# ZeroCrossDetector.net
KiCad netlist of a schematic drawn in Altium Designer
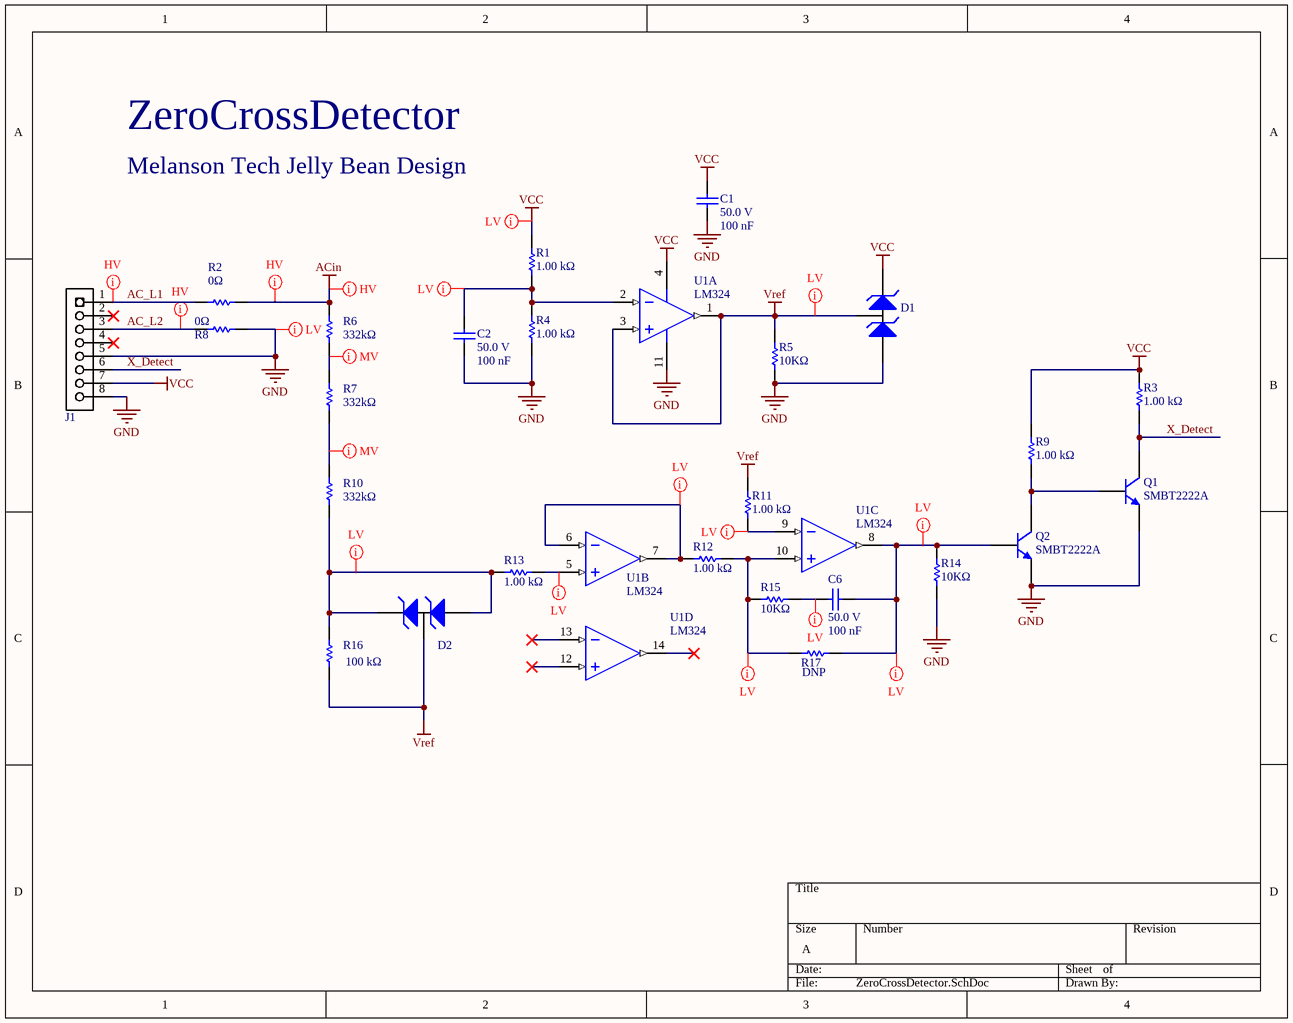
[diagram p0: ZeroCrossDetector.SchDoc]

(export (version "E")
  (design (tool "Eeschema 10.0.6"))
  (components
    (comp (ref "C1")
      (value "08055C104JAT2A")
      (footprint "Cap,0805")
      (description "Capacitor; Ceramic; Cap 0.1 uF; Tol 5%; Vol-Rtg 50 VDC; SMT; 0805; X7R; Tape & Reel")
      (fields (field (name "VOLTAGE RATING (DC)") "50.0 V") (field (name "CAPACITANCE") "100 nF"))
      (libsource (lib "Master Nov2021") (part "Cap,0805,100nf,50V,5%,08055C104JAT2A"))
    )
    (comp (ref "C2")
      (value "08055C104JAT2A")
      (footprint "Cap,0805")
      (description "Capacitor; Ceramic; Cap 0.1 uF; Tol 5%; Vol-Rtg 50 VDC; SMT; 0805; X7R; Tape & Reel")
      (fields (field (name "VOLTAGE RATING (DC)") "50.0 V") (field (name "CAPACITANCE") "100 nF"))
      (libsource (lib "Master Nov2021") (part "Cap,0805,100nf,50V,5%,08055C104JAT2A"))
    )
    (comp (ref "C6")
      (value "08055C104JAT2A")
      (footprint "Cap,0805")
      (description "Capacitor; Ceramic; Cap 0.1 uF; Tol 5%; Vol-Rtg 50 VDC; SMT; 0805; X7R; Tape & Reel")
      (fields (field (name "VOLTAGE RATING (DC)") "50.0 V") (field (name "CAPACITANCE") "100 nF"))
      (libsource (lib "Master Nov2021") (part "Cap,0805,100nf,50V,5%,08055C104JAT2A"))
    )
    (comp (ref "D1")
      (value "BAT54SLT1G")
      (footprint "SOT23-3")
      (fields (field (name "BASE PART NUMBER") "BAT54SL") (field (name "MANUFACTURER") "ON Semiconductor"))
      (libsource (lib "Master Nov2021") (part "Diode,Shottky,Array,Series,30V,200mA,BAT54SLT1G"))
    )
    (comp (ref "D2")
      (value "BAT54SLT1G")
      (footprint "SOT23-3")
      (fields (field (name "BASE PART NUMBER") "BAT54SL") (field (name "MANUFACTURER") "ON Semiconductor"))
      (libsource (lib "Master Nov2021") (part "Diode,Shottky,Array,Series,30V,200mA,BAT54SLT1G"))
    )
    (comp (ref "J1")
      (value "HEADER,0.1\",8Pin,SinlgeRow")
      (footprint "Header,8Pin,SingleRow, RA,0.1\"")
      (libsource (lib "Master Nov2021") (part "HEADER,0.1{dblquote},8Pin,SinlgeRow"))
    )
    (comp (ref "Logo1")
      (value "Open Source Logo")
      (footprint "Symbol,Open Source")
      (description "Open Source Silk Screen Logo")
      (libsource (lib "Master Mar2024") (part "Symbol,Open Source"))
    )
    (comp (ref "Q1")
      (value "SMBT2222A")
      (footprint "SOT23-3")
      (description "NPN Silicon Switching Transistor, 40 V VCEO, 600 mA IC, SOT23, Reel, Green")
      (fields (field (name "MFG P/N") "SMBT2222A"))
      (libsource (lib "Master Nov2021") (part "Trans,40V,600mA,0.33W, SMBT2222A"))
    )
    (comp (ref "Q2")
      (value "SMBT2222A")
      (footprint "SOT23-3")
      (description "NPN Silicon Switching Transistor, 40 V VCEO, 600 mA IC, SOT23, Reel, Green")
      (fields (field (name "MFG P/N") "SMBT2222A"))
      (libsource (lib "Master Nov2021") (part "Trans,40V,600mA,0.33W, SMBT2222A"))
    )
    (comp (ref "R1")
      (value "Vishay CRCW08051K00JNEA")
      (footprint "res, 0805, HD")
      (description "Res Thick Film 0805 1K Ohm 5% 0.125W(1/8W) ±200ppm/C Molded SMD Automotive Paper T/R")
      (fields
        (field (name "MANUFACTURER PART NUMBER") "CRCW08051K00JNEA")
        (field (name "RESISTANCE") "1.00 kΩ")
      )
      (libsource (lib "Master Nov2021") (part "Res,0805,1.00 kΩ,5%,200ppm,CRCW08051K00JNEA"))
    )
    (comp (ref "R2")
      (value "Res1")
      (footprint "Res,1206")
      (fields (field (name "RESISTANCE") "0Ω"))
      (libsource (lib "Master Nov2021") (part "Res,1206,Generic"))
    )
    (comp (ref "R3")
      (value "Vishay CRCW08051K00JNEA")
      (footprint "res, 0805, HD")
      (description "Res Thick Film 0805 1K Ohm 5% 0.125W(1/8W) ±200ppm/C Molded SMD Automotive Paper T/R")
      (fields
        (field (name "MANUFACTURER PART NUMBER") "CRCW08051K00JNEA")
        (field (name "RESISTANCE") "1.00 kΩ")
      )
      (libsource (lib "Master Nov2021") (part "Res,0805,1.00 kΩ,5%,200ppm,CRCW08051K00JNEA"))
    )
    (comp (ref "R4")
      (value "Vishay CRCW08051K00JNEA")
      (footprint "res, 0805, HD")
      (description "Res Thick Film 0805 1K Ohm 5% 0.125W(1/8W) ±200ppm/C Molded SMD Automotive Paper T/R")
      (fields
        (field (name "MANUFACTURER PART NUMBER") "CRCW08051K00JNEA")
        (field (name "RESISTANCE") "1.00 kΩ")
      )
      (libsource (lib "Master Nov2021") (part "Res,0805,1.00 kΩ,5%,200ppm,CRCW08051K00JNEA"))
    )
    (comp (ref "R5")
      (value "Vishay / Dale CRCW080510K0FKTA")
      (footprint "res, 0805, HD")
      (description "RES SMD 10K OHM 1% 1/8W 0805")
      (fields (field (name "RESISTANCE") "10KΩ"))
      (libsource (lib "Master Nov2021") (part "Res,0805,10.0kΩ,1%,100 ppm,CRCW080510K0FKTA"))
    )
    (comp (ref "R6")
      (value "RT0805BRD07332KL")
      (footprint "res, 0805, HD")
      (description "Thin Film Resistors - SMD 1/8W 332K ohm .1% 25ppm")
      (fields (field (name "RESISTANCE") "332kΩ"))
      (libsource (lib "Master Nov2021") (part "Res,0805,332k,0.1%,±25ppm/°C,RT0805BRD07332KL"))
    )
    (comp (ref "R7")
      (value "RT0805BRD07332KL")
      (footprint "res, 0805, HD")
      (description "Thin Film Resistors - SMD 1/8W 332K ohm .1% 25ppm")
      (fields (field (name "RESISTANCE") "332kΩ"))
      (libsource (lib "Master Nov2021") (part "Res,0805,332k,0.1%,±25ppm/°C,RT0805BRD07332KL"))
    )
    (comp (ref "R8")
      (value "Res1")
      (footprint "Res,1206")
      (fields (field (name "RESISTANCE") "0Ω"))
      (libsource (lib "Master Nov2021") (part "Res,1206,Generic"))
    )
    (comp (ref "R9")
      (value "Vishay CRCW08051K00JNEA")
      (footprint "res, 0805, HD")
      (description "Res Thick Film 0805 1K Ohm 5% 0.125W(1/8W) ±200ppm/C Molded SMD Automotive Paper T/R")
      (fields
        (field (name "MANUFACTURER PART NUMBER") "CRCW08051K00JNEA")
        (field (name "RESISTANCE") "1.00 kΩ")
      )
      (libsource (lib "Master Nov2021") (part "Res,0805,1.00 kΩ,5%,200ppm,CRCW08051K00JNEA"))
    )
    (comp (ref "R10")
      (value "RT0805BRD07332KL")
      (footprint "res, 0805, HD")
      (description "Thin Film Resistors - SMD 1/8W 332K ohm .1% 25ppm")
      (fields (field (name "RESISTANCE") "332kΩ"))
      (libsource (lib "Master Nov2021") (part "Res,0805,332k,0.1%,±25ppm/°C,RT0805BRD07332KL"))
    )
    (comp (ref "R11")
      (value "Vishay CRCW08051K00JNEA")
      (footprint "res, 0805, HD")
      (description "Res Thick Film 0805 1K Ohm 5% 0.125W(1/8W) ±200ppm/C Molded SMD Automotive Paper T/R")
      (fields
        (field (name "MANUFACTURER PART NUMBER") "CRCW08051K00JNEA")
        (field (name "RESISTANCE") "1.00 kΩ")
      )
      (libsource (lib "Master Nov2021") (part "Res,0805,1.00 kΩ,5%,200ppm,CRCW08051K00JNEA"))
    )
    (comp (ref "R12")
      (value "Vishay CRCW08051K00JNEA")
      (footprint "res, 0805, HD")
      (description "Res Thick Film 0805 1K Ohm 5% 0.125W(1/8W) ±200ppm/C Molded SMD Automotive Paper T/R")
      (fields
        (field (name "MANUFACTURER PART NUMBER") "CRCW08051K00JNEA")
        (field (name "RESISTANCE") "1.00 kΩ")
      )
      (libsource (lib "Master Nov2021") (part "Res,0805,1.00 kΩ,5%,200ppm,CRCW08051K00JNEA"))
    )
    (comp (ref "R13")
      (value "Vishay CRCW08051K00JNEA")
      (footprint "res, 0805, HD")
      (description "Res Thick Film 0805 1K Ohm 5% 0.125W(1/8W) ±200ppm/C Molded SMD Automotive Paper T/R")
      (fields
        (field (name "MANUFACTURER PART NUMBER") "CRCW08051K00JNEA")
        (field (name "RESISTANCE") "1.00 kΩ")
      )
      (libsource (lib "Master Nov2021") (part "Res,0805,1.00 kΩ,5%,200ppm,CRCW08051K00JNEA"))
    )
    (comp (ref "R14")
      (value "Vishay / Dale CRCW080510K0FKTA")
      (footprint "res, 0805, HD")
      (description "RES SMD 10K OHM 1% 1/8W 0805")
      (fields (field (name "RESISTANCE") "10KΩ"))
      (libsource (lib "Master Nov2021") (part "Res,0805,10.0kΩ,1%,100 ppm,CRCW080510K0FKTA"))
    )
    (comp (ref "R15")
      (value "Vishay / Dale CRCW080510K0FKTA")
      (footprint "res, 0805, HD")
      (description "RES SMD 10K OHM 1% 1/8W 0805")
      (fields (field (name "RESISTANCE") "10KΩ"))
      (libsource (lib "Master Nov2021") (part "Res,0805,10.0kΩ,1%,100 ppm,CRCW080510K0FKTA"))
    )
    (comp (ref "R16")
      (value "CRCW0805100KFKEA")
      (footprint "res, 0805, HD")
      (description "100 kOhms ±1% 0.125W, 1/8W Chip Resistor 0805 (2012 Metric) Thick Film")
      (fields (field (name "MANUFACTURER") "Vishay") (field (name "RESISTANCE") "100 kΩ"))
      (libsource (lib "Master Nov2021") (part "Res,0805,100kΩ,1%,100ppm,CRCW0805100KFKEA"))
    )
    (comp (ref "R17")
      (value "DNP")
      (footprint "res, 0805, HD")
      (libsource (lib "Master Nov2021") (part "Res,0805,Generic"))
    )
    (comp (ref "U1")
      (value "LM324ADR2G")
      (footprint "SOIC-14")
      (fields (field (name "MFG P/N") "LM324"))
      (libsource (lib "Master Nov2021") (part "OPAMP, Quad circuit, 1Mhz, SOIC-14,SMD, LM324ADR2G"))
    )
  )
  (nets
    (net (code "1") (name "/AC_L1") (class "Default")
      (node (ref "J1") (pin "1") (pintype "passive"))
      (node (ref "R2") (pin "1") (pinfunction "1_1") (pintype "passive"))
    )
    (net (code "2") (name "/AC_L2") (class "Default")
      (node (ref "J1") (pin "3") (pintype "passive"))
      (node (ref "R8") (pin "2") (pinfunction "2_2") (pintype "passive"))
    )
    (net (code "3") (name "/X_Detect") (class "Default")
      (node (ref "J1") (pin "6") (pintype "passive"))
      (node (ref "Q1") (pin "3") (pinfunction "C_3") (pintype "passive"))
      (node (ref "R3") (pin "1") (pinfunction "1_1") (pintype "passive"))
    )
    (net (code "4") (name "ACin") (class "Default")
      (node (ref "R2") (pin "2") (pinfunction "2_2") (pintype "passive"))
      (node (ref "R6") (pin "2") (pinfunction "2_2") (pintype "passive"))
    )
    (net (code "5") (name "GND") (class "Default")
      (node (ref "C1") (pin "1") (pinfunction "1_1") (pintype "passive"))
      (node (ref "C2") (pin "1") (pinfunction "1_1") (pintype "passive"))
      (node (ref "D1") (pin "1") (pinfunction "A_1") (pintype "passive"))
      (node (ref "J1") (pin "5") (pintype "passive"))
      (node (ref "J1") (pin "8") (pintype "passive"))
      (node (ref "Q1") (pin "2") (pinfunction "E_2") (pintype "passive"))
      (node (ref "Q2") (pin "2") (pinfunction "E_2") (pintype "passive"))
      (node (ref "R14") (pin "1") (pinfunction "1_1") (pintype "passive"))
      (node (ref "R4") (pin "2") (pinfunction "2_2") (pintype "passive"))
      (node (ref "R5") (pin "1") (pinfunction "1_1") (pintype "passive"))
      (node (ref "R8") (pin "1") (pinfunction "1_1") (pintype "passive"))
      (node (ref "U1") (pin "11") (pinfunction "GND_11") (pintype "power_in"))
    )
    (net (code "6") (name "Net-(C6-Pad2)") (class "Default")
      (node (ref "C6") (pin "2") (pinfunction "2_2") (pintype "passive"))
      (node (ref "R15") (pin "2") (pinfunction "2_2") (pintype "passive"))
    )
    (net (code "7") (name "Net-(D2-A)") (class "Default")
      (node (ref "D2") (pin "1") (pinfunction "A_1") (pintype "passive"))
      (node (ref "D2") (pin "2") (pinfunction "K_2") (pintype "passive"))
      (node (ref "R10") (pin "1") (pinfunction "1_1") (pintype "passive"))
      (node (ref "R13") (pin "1") (pinfunction "1_1") (pintype "passive"))
      (node (ref "R16") (pin "2") (pinfunction "2_2") (pintype "passive"))
    )
    (net (code "8") (name "Net-(Q1-B)") (class "Default")
      (node (ref "Q1") (pin "1") (pinfunction "B_1") (pintype "passive"))
      (node (ref "Q2") (pin "3") (pinfunction "C_3") (pintype "passive"))
      (node (ref "R9") (pin "1") (pinfunction "1_1") (pintype "passive"))
    )
    (net (code "9") (name "Net-(Q2-B)") (class "Default")
      (node (ref "C6") (pin "1") (pinfunction "1_1") (pintype "passive"))
      (node (ref "Q2") (pin "1") (pinfunction "B_1") (pintype "passive"))
      (node (ref "R14") (pin "2") (pinfunction "2_2") (pintype "passive"))
      (node (ref "R17") (pin "1") (pinfunction "1_1") (pintype "passive"))
      (node (ref "U1") (pin "8") (pinfunction "OUT3_8") (pintype "output"))
    )
    (net (code "10") (name "Net-(R6-Pad1)") (class "Default")
      (node (ref "R6") (pin "1") (pinfunction "1_1") (pintype "passive"))
      (node (ref "R7") (pin "2") (pinfunction "2_2") (pintype "passive"))
    )
    (net (code "11") (name "Net-(R10-Pad2)") (class "Default")
      (node (ref "R10") (pin "2") (pinfunction "2_2") (pintype "passive"))
      (node (ref "R7") (pin "1") (pinfunction "1_1") (pintype "passive"))
    )
    (net (code "12") (name "Net-(U1A-IN1-)") (class "Default")
      (node (ref "C2") (pin "2") (pinfunction "2_2") (pintype "passive"))
      (node (ref "R1") (pin "2") (pinfunction "2_2") (pintype "passive"))
      (node (ref "R4") (pin "1") (pinfunction "1_1") (pintype "passive"))
      (node (ref "U1") (pin "2") (pinfunction "IN1-_2") (pintype "input"))
    )
    (net (code "13") (name "Net-(U1B-IN2+)") (class "Default")
      (node (ref "R13") (pin "2") (pinfunction "2_2") (pintype "passive"))
      (node (ref "U1") (pin "5") (pinfunction "IN2+_5") (pintype "input"))
    )
    (net (code "14") (name "Net-(U1B-IN2-)") (class "Default")
      (node (ref "R12") (pin "1") (pinfunction "1_1") (pintype "passive"))
      (node (ref "U1") (pin "6") (pinfunction "IN2-_6") (pintype "input"))
      (node (ref "U1") (pin "7") (pinfunction "OUT2_7") (pintype "output"))
    )
    (net (code "15") (name "Net-(U1C-IN3+)") (class "Default")
      (node (ref "R12") (pin "2") (pinfunction "2_2") (pintype "passive"))
      (node (ref "R15") (pin "1") (pinfunction "1_1") (pintype "passive"))
      (node (ref "R17") (pin "2") (pinfunction "2_2") (pintype "passive"))
      (node (ref "U1") (pin "10") (pinfunction "IN3+_10") (pintype "input"))
    )
    (net (code "16") (name "Net-(U1C-IN3-)") (class "Default")
      (node (ref "R11") (pin "1") (pinfunction "1_1") (pintype "passive"))
      (node (ref "U1") (pin "9") (pinfunction "IN3-_9") (pintype "input"))
    )
    (net (code "17") (name "VCC") (class "Default")
      (node (ref "C1") (pin "2") (pinfunction "2_2") (pintype "passive"))
      (node (ref "D1") (pin "2") (pinfunction "K_2") (pintype "passive"))
      (node (ref "J1") (pin "7") (pintype "passive"))
      (node (ref "R1") (pin "1") (pinfunction "1_1") (pintype "passive"))
      (node (ref "R3") (pin "2") (pinfunction "2_2") (pintype "passive"))
      (node (ref "R9") (pin "2") (pinfunction "2_2") (pintype "passive"))
      (node (ref "U1") (pin "4") (pinfunction "VCC_4") (pintype "power_in"))
    )
    (net (code "18") (name "Vref") (class "Default")
      (node (ref "D1") (pin "3") (pinfunction "AK_3") (pintype "passive"))
      (node (ref "D2") (pin "3") (pinfunction "AK_3") (pintype "passive"))
      (node (ref "R11") (pin "2") (pinfunction "2_2") (pintype "passive"))
      (node (ref "R16") (pin "1") (pinfunction "1_1") (pintype "passive"))
      (node (ref "R5") (pin "2") (pinfunction "2_2") (pintype "passive"))
      (node (ref "U1") (pin "1") (pinfunction "OUT1_1") (pintype "output"))
      (node (ref "U1") (pin "3") (pinfunction "IN1+_3") (pintype "input"))
    )
    (net (code "19") (name "unconnected-(J1-Pad2)") (class "Default")
      (node (ref "J1") (pin "2") (pintype "passive+no_connect"))
    )
    (net (code "20") (name "unconnected-(J1-Pad4)") (class "Default")
      (node (ref "J1") (pin "4") (pintype "passive+no_connect"))
    )
    (net (code "21") (name "unconnected-(U1D-IN4+-Pad12)") (class "Default")
      (node (ref "U1") (pin "12") (pinfunction "IN4+_12") (pintype "input+no_connect"))
    )
    (net (code "22") (name "unconnected-(U1D-IN4--Pad13)") (class "Default")
      (node (ref "U1") (pin "13") (pinfunction "IN4-_13") (pintype "input+no_connect"))
    )
    (net (code "23") (name "unconnected-(U1D-OUT4-Pad14)") (class "Default")
      (node (ref "U1") (pin "14") (pinfunction "OUT4_14") (pintype "output+no_connect"))
    )
  )
)
